# phase_1.net
KiCad netlist of a schematic drawn in EAGLE
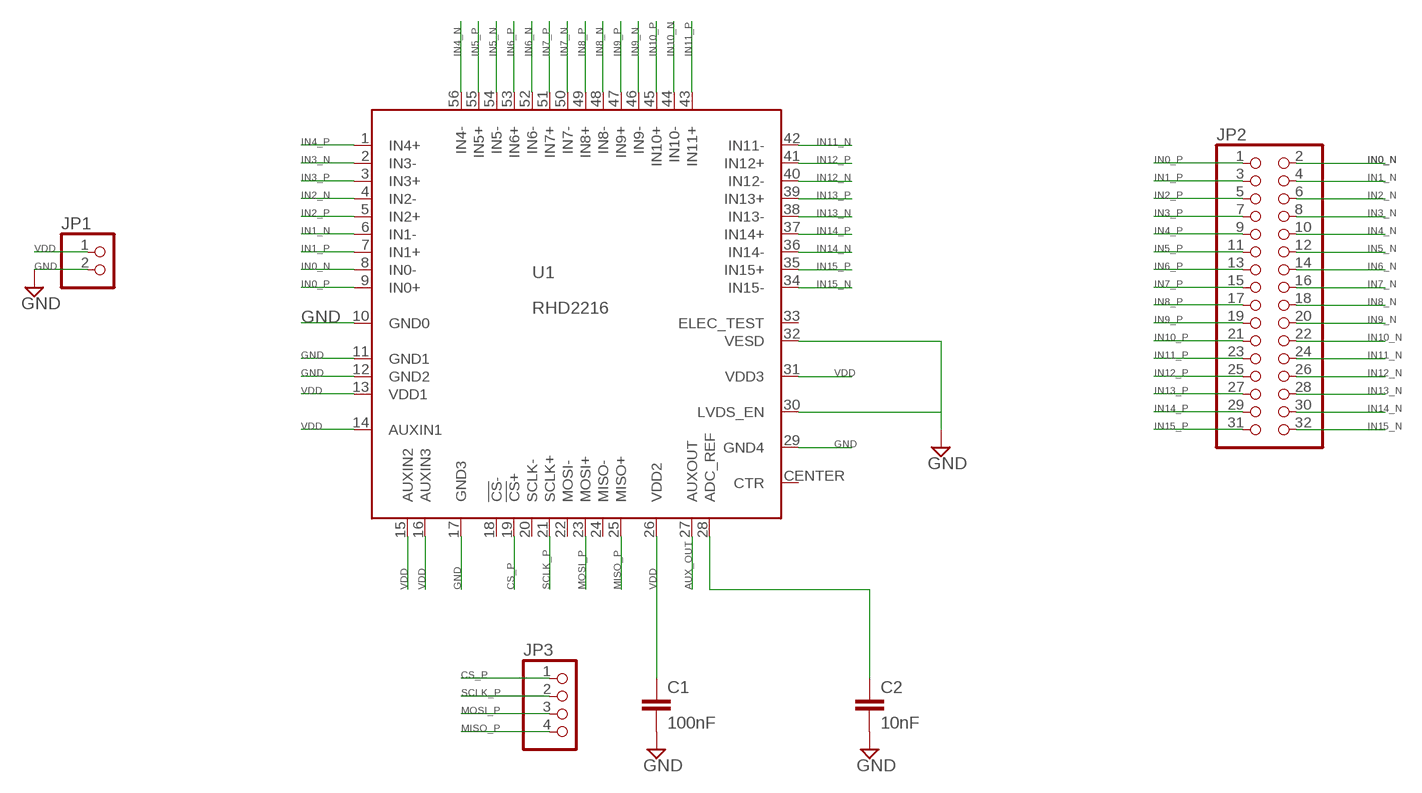
[diagram p0: schematic, sheet 1]

(export (version "E")
  (design (tool "Eeschema 10.0.6"))
  (components
    (comp (ref "C1")
      (value "100nF")
      (footprint "eagle-import:C2.5-2")
      (libsource (lib "eagle-import") (part "C2.5/2"))
    )
    (comp (ref "C2")
      (value "10nF")
      (footprint "eagle-import:C2.5-2")
      (libsource (lib "eagle-import") (part "C2.5/2"))
    )
    (comp (ref "JP1")
      (value "PINHD-1X2")
      (footprint "eagle-import:1X02")
      (libsource (lib "eagle-import") (part "PINHD-1X2"))
    )
    (comp (ref "JP2")
      (value "PINHD-2X16")
      (footprint "eagle-import:2X16")
      (libsource (lib "eagle-import") (part "PINHD-2X16"))
    )
    (comp (ref "JP3")
      (value "PINHD-1X4")
      (footprint "eagle-import:1X04")
      (libsource (lib "eagle-import") (part "PINHD-1X4"))
    )
    (comp (ref "U1")
      (value "RHD2216")
      (footprint "eagle-import:ZIF_QFN56_8_X_8_MLF00056A1")
      (libsource (lib "eagle-import") (part "RHD2216"))
    )
  )
  (nets
    (net (code "1") (name "/AUX_OUT") (class "Default")
      (node (ref "U1") (pin "27") (pinfunction "AUXOUT_27") (pintype "tri_state"))
    )
    (net (code "2") (name "/CS_P") (class "Default")
      (node (ref "JP3") (pin "1") (pinfunction "1_1") (pintype "passive"))
      (node (ref "U1") (pin "19") (pinfunction "~{CS}+_19") (pintype "input"))
    )
    (net (code "3") (name "/CTR") (class "Default")
      (node (ref "U1") (pin "CENTER") (pinfunction "CTR_CENTER") (pintype "power_in"))
    )
    (net (code "4") (name "/IN0_N") (class "Default")
      (node (ref "JP2") (pin "2") (pinfunction "2_2") (pintype "passive"))
      (node (ref "U1") (pin "8") (pinfunction "IN0-_8") (pintype "input"))
    )
    (net (code "5") (name "/IN0_P") (class "Default")
      (node (ref "JP2") (pin "1") (pinfunction "1_1") (pintype "passive"))
      (node (ref "U1") (pin "9") (pinfunction "IN0+_9") (pintype "input"))
    )
    (net (code "6") (name "/IN1_N") (class "Default")
      (node (ref "JP2") (pin "4") (pinfunction "4_4") (pintype "passive"))
      (node (ref "U1") (pin "6") (pinfunction "IN1-_6") (pintype "input"))
    )
    (net (code "7") (name "/IN1_P") (class "Default")
      (node (ref "JP2") (pin "3") (pinfunction "3_3") (pintype "passive"))
      (node (ref "U1") (pin "7") (pinfunction "IN1+_7") (pintype "input"))
    )
    (net (code "8") (name "/IN2_N") (class "Default")
      (node (ref "JP2") (pin "6") (pinfunction "6_6") (pintype "passive"))
      (node (ref "U1") (pin "4") (pinfunction "IN2-_4") (pintype "input"))
    )
    (net (code "9") (name "/IN2_P") (class "Default")
      (node (ref "JP2") (pin "5") (pinfunction "5_5") (pintype "passive"))
      (node (ref "U1") (pin "5") (pinfunction "IN2+_5") (pintype "input"))
    )
    (net (code "10") (name "/IN3_N") (class "Default")
      (node (ref "JP2") (pin "8") (pinfunction "8_8") (pintype "passive"))
      (node (ref "U1") (pin "2") (pinfunction "IN3-_2") (pintype "input"))
    )
    (net (code "11") (name "/IN3_P") (class "Default")
      (node (ref "JP2") (pin "7") (pinfunction "7_7") (pintype "passive"))
      (node (ref "U1") (pin "3") (pinfunction "IN3+_3") (pintype "input"))
    )
    (net (code "12") (name "/IN4_N") (class "Default")
      (node (ref "JP2") (pin "10") (pinfunction "10_10") (pintype "passive"))
      (node (ref "U1") (pin "56") (pinfunction "IN4-_56") (pintype "input"))
    )
    (net (code "13") (name "/IN4_P") (class "Default")
      (node (ref "JP2") (pin "9") (pinfunction "9_9") (pintype "passive"))
      (node (ref "U1") (pin "1") (pinfunction "IN4+_1") (pintype "input"))
    )
    (net (code "14") (name "/IN5_N") (class "Default")
      (node (ref "JP2") (pin "12") (pinfunction "12_12") (pintype "passive"))
      (node (ref "U1") (pin "54") (pinfunction "IN5-_54") (pintype "input"))
    )
    (net (code "15") (name "/IN5_P") (class "Default")
      (node (ref "JP2") (pin "11") (pinfunction "11_11") (pintype "passive"))
      (node (ref "U1") (pin "55") (pinfunction "IN5+_55") (pintype "input"))
    )
    (net (code "16") (name "/IN6_N") (class "Default")
      (node (ref "JP2") (pin "14") (pinfunction "14_14") (pintype "passive"))
      (node (ref "U1") (pin "52") (pinfunction "IN6-_52") (pintype "input"))
    )
    (net (code "17") (name "/IN6_P") (class "Default")
      (node (ref "JP2") (pin "13") (pinfunction "13_13") (pintype "passive"))
      (node (ref "U1") (pin "53") (pinfunction "IN6+_53") (pintype "input"))
    )
    (net (code "18") (name "/IN7_N") (class "Default")
      (node (ref "JP2") (pin "16") (pinfunction "16_16") (pintype "passive"))
      (node (ref "U1") (pin "50") (pinfunction "IN7-_50") (pintype "input"))
    )
    (net (code "19") (name "/IN7_P") (class "Default")
      (node (ref "JP2") (pin "15") (pinfunction "15_15") (pintype "passive"))
      (node (ref "U1") (pin "51") (pinfunction "IN7+_51") (pintype "input"))
    )
    (net (code "20") (name "/IN8_N") (class "Default")
      (node (ref "JP2") (pin "18") (pinfunction "18_18") (pintype "passive"))
      (node (ref "U1") (pin "48") (pinfunction "IN8-_48") (pintype "input"))
    )
    (net (code "21") (name "/IN8_P") (class "Default")
      (node (ref "JP2") (pin "17") (pinfunction "17_17") (pintype "passive"))
      (node (ref "U1") (pin "49") (pinfunction "IN8+_49") (pintype "input"))
    )
    (net (code "22") (name "/IN9_N") (class "Default")
      (node (ref "JP2") (pin "20") (pinfunction "20_20") (pintype "passive"))
      (node (ref "U1") (pin "46") (pinfunction "IN9-_46") (pintype "input"))
    )
    (net (code "23") (name "/IN9_P") (class "Default")
      (node (ref "JP2") (pin "19") (pinfunction "19_19") (pintype "passive"))
      (node (ref "U1") (pin "47") (pinfunction "IN9+_47") (pintype "input"))
    )
    (net (code "24") (name "/IN10_N") (class "Default")
      (node (ref "JP2") (pin "22") (pinfunction "22_22") (pintype "passive"))
      (node (ref "U1") (pin "44") (pinfunction "IN10-_44") (pintype "input"))
    )
    (net (code "25") (name "/IN10_P") (class "Default")
      (node (ref "JP2") (pin "21") (pinfunction "21_21") (pintype "passive"))
      (node (ref "U1") (pin "45") (pinfunction "IN10+_45") (pintype "input"))
    )
    (net (code "26") (name "/IN11_N") (class "Default")
      (node (ref "JP2") (pin "24") (pinfunction "24_24") (pintype "passive"))
      (node (ref "U1") (pin "42") (pinfunction "IN11-_42") (pintype "input"))
    )
    (net (code "27") (name "/IN11_P") (class "Default")
      (node (ref "JP2") (pin "23") (pinfunction "23_23") (pintype "passive"))
      (node (ref "U1") (pin "43") (pinfunction "IN11+_43") (pintype "input"))
    )
    (net (code "28") (name "/IN12_N") (class "Default")
      (node (ref "JP2") (pin "26") (pinfunction "26_26") (pintype "passive"))
      (node (ref "U1") (pin "40") (pinfunction "IN12-_40") (pintype "input"))
    )
    (net (code "29") (name "/IN12_P") (class "Default")
      (node (ref "JP2") (pin "25") (pinfunction "25_25") (pintype "passive"))
      (node (ref "U1") (pin "41") (pinfunction "IN12+_41") (pintype "input"))
    )
    (net (code "30") (name "/IN13_N") (class "Default")
      (node (ref "JP2") (pin "28") (pinfunction "28_28") (pintype "passive"))
      (node (ref "U1") (pin "38") (pinfunction "IN13-_38") (pintype "input"))
    )
    (net (code "31") (name "/IN13_P") (class "Default")
      (node (ref "JP2") (pin "27") (pinfunction "27_27") (pintype "passive"))
      (node (ref "U1") (pin "39") (pinfunction "IN13+_39") (pintype "input"))
    )
    (net (code "32") (name "/IN14_N") (class "Default")
      (node (ref "JP2") (pin "30") (pinfunction "30_30") (pintype "passive"))
      (node (ref "U1") (pin "36") (pinfunction "IN14-_36") (pintype "input"))
    )
    (net (code "33") (name "/IN14_P") (class "Default")
      (node (ref "JP2") (pin "29") (pinfunction "29_29") (pintype "passive"))
      (node (ref "U1") (pin "37") (pinfunction "IN14+_37") (pintype "input"))
    )
    (net (code "34") (name "/IN15_N") (class "Default")
      (node (ref "JP2") (pin "32") (pinfunction "32_32") (pintype "passive"))
      (node (ref "U1") (pin "34") (pinfunction "IN15-_34") (pintype "input"))
    )
    (net (code "35") (name "/IN15_P") (class "Default")
      (node (ref "JP2") (pin "31") (pinfunction "31_31") (pintype "passive"))
      (node (ref "U1") (pin "35") (pinfunction "IN15+_35") (pintype "input"))
    )
    (net (code "36") (name "/MISO_P") (class "Default")
      (node (ref "JP3") (pin "4") (pinfunction "4_4") (pintype "passive"))
      (node (ref "U1") (pin "25") (pinfunction "MISO+_25") (pintype "output"))
    )
    (net (code "37") (name "/MOSI_P") (class "Default")
      (node (ref "JP3") (pin "3") (pinfunction "3_3") (pintype "passive"))
      (node (ref "U1") (pin "23") (pinfunction "MOSI+_23") (pintype "input"))
    )
    (net (code "38") (name "/SCLK_P") (class "Default")
      (node (ref "JP3") (pin "2") (pinfunction "2_2") (pintype "passive"))
      (node (ref "U1") (pin "21") (pinfunction "SCLK+_21") (pintype "input"))
    )
    (net (code "39") (name "/VDD") (class "Default")
      (node (ref "C1") (pin "1") (pinfunction "1_1") (pintype "passive"))
      (node (ref "JP1") (pin "1") (pinfunction "1_1") (pintype "passive"))
      (node (ref "U1") (pin "13") (pinfunction "VDD1_13") (pintype "power_in"))
      (node (ref "U1") (pin "14") (pinfunction "AUXIN1_14") (pintype "input"))
      (node (ref "U1") (pin "15") (pinfunction "AUXIN2_15") (pintype "input"))
      (node (ref "U1") (pin "16") (pinfunction "AUXIN3_16") (pintype "input"))
      (node (ref "U1") (pin "26") (pinfunction "VDD2_26") (pintype "power_in"))
      (node (ref "U1") (pin "31") (pinfunction "VDD3_31") (pintype "power_in"))
    )
    (net (code "40") (name "GND") (class "Default")
      (node (ref "C1") (pin "2") (pinfunction "2_2") (pintype "passive"))
      (node (ref "C2") (pin "2") (pinfunction "2_2") (pintype "passive"))
      (node (ref "JP1") (pin "2") (pinfunction "2_2") (pintype "passive"))
      (node (ref "U1") (pin "10") (pinfunction "GND0_10") (pintype "input"))
      (node (ref "U1") (pin "11") (pinfunction "GND1_11") (pintype "power_in"))
      (node (ref "U1") (pin "12") (pinfunction "GND2_12") (pintype "power_in"))
      (node (ref "U1") (pin "17") (pinfunction "GND3_17") (pintype "power_in"))
      (node (ref "U1") (pin "29") (pinfunction "GND4_29") (pintype "power_in"))
      (node (ref "U1") (pin "30") (pinfunction "LVDS_EN_30") (pintype "input"))
      (node (ref "U1") (pin "32") (pinfunction "VESD_32") (pintype "power_in"))
    )
    (net (code "41") (name "Net-(U1-ADC_REF)") (class "Default")
      (node (ref "C2") (pin "1") (pinfunction "1_1") (pintype "passive"))
      (node (ref "U1") (pin "28") (pinfunction "ADC_REF_28") (pintype "passive"))
    )
    (net (code "42") (name "unconnected-(U1-ELEC_TEST-Pad33)") (class "Default")
      (node (ref "U1") (pin "33") (pinfunction "ELEC_TEST_33") (pintype "input"))
    )
    (net (code "43") (name "unconnected-(U1-MISO--Pad24)") (class "Default")
      (node (ref "U1") (pin "24") (pinfunction "MISO-_24") (pintype "output"))
    )
    (net (code "44") (name "unconnected-(U1-MOSI--Pad22)") (class "Default")
      (node (ref "U1") (pin "22") (pinfunction "MOSI-_22") (pintype "input"))
    )
    (net (code "45") (name "unconnected-(U1-SCLK--Pad20)") (class "Default")
      (node (ref "U1") (pin "20") (pinfunction "SCLK-_20") (pintype "input"))
    )
    (net (code "46") (name "unconnected-(U1-~{CS}--Pad18)") (class "Default")
      (node (ref "U1") (pin "18") (pinfunction "~{CS}-_18") (pintype "input"))
    )
  )
)
